# AUDIO_JACK.net
KiCad netlist of a schematic drawn in Altium Designer
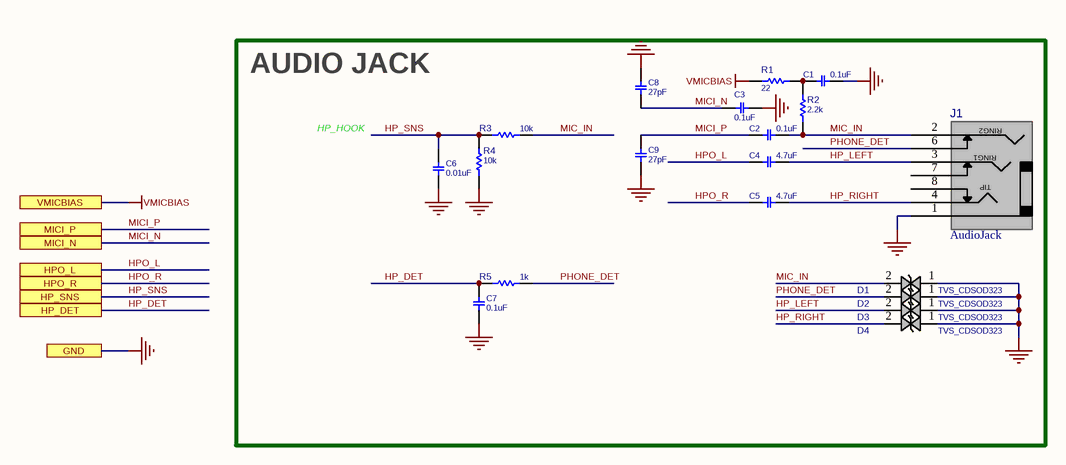
[diagram p0: AUDIO_JACK.SchDoc]

(export (version "E")
  (design (tool "Eeschema 10.0.6"))
  (components
    (comp (ref "C1")
      (value "0.1uF")
      (footprint "C0402")
      (description "CAP, MLCC")
      (fields (field (name "MANF_P#") "GRM155R61E104") (field (name "MANF") "Murata"))
      (libsource (lib "passive_smd") (part "CAP_SMD_MLCC"))
    )
    (comp (ref "C2")
      (value "0.1uF")
      (footprint "C0402")
      (description "CAP, MLCC")
      (fields (field (name "MANF_P#") "GRM155R61E104") (field (name "MANF") "Murata"))
      (libsource (lib "passive_smd") (part "CAP_SMD_MLCC"))
    )
    (comp (ref "C3")
      (value "0.1uF")
      (footprint "C0402")
      (description "CAP, MLCC")
      (fields (field (name "MANF_P#") "GRM155R61E104") (field (name "MANF") "Murata"))
      (libsource (lib "passive_smd") (part "CAP_SMD_MLCC"))
    )
    (comp (ref "C4")
      (value "4.7uF")
      (footprint "C0402")
      (description "CAP, MLCC")
      (fields (field (name "MANF_P#") "CL05A475MP5NRNC") (field (name "MANF") "Samsung"))
      (libsource (lib "mlcc_smd_passive") (part "CAP_SMD_MLCC_100n50TDK"))
    )
    (comp (ref "C5")
      (value "4.7uF")
      (footprint "C0402")
      (description "CAP, MLCC")
      (fields (field (name "MANF_P#") "CL05A475MP5NRNC") (field (name "MANF") "Samsung"))
      (libsource (lib "mlcc_smd_passive") (part "CAP_SMD_MLCC_100n50TDK"))
    )
    (comp (ref "C6")
      (value "0.01uF")
      (footprint "C0402")
      (description "CAP, MLCC")
      (libsource (lib "passive_smd") (part "CAP_SMD_MLCC"))
    )
    (comp (ref "C7")
      (value "0.1uF")
      (footprint "C0402")
      (description "CAP, MLCC")
      (fields (field (name "MANF_P#") "GRM155R61E104") (field (name "MANF") "Murata"))
      (libsource (lib "passive_smd") (part "CAP_SMD_MLCC"))
    )
    (comp (ref "C8")
      (value "27pF")
      (footprint "C0402")
      (description "CAP, MLCC")
      (fields (field (name "MANF_P#") "CC0402JRNPO9BN270") (field (name "MANF") "Yageo"))
      (libsource (lib "passive_smd") (part "CAP_SMD_MLCC"))
    )
    (comp (ref "C9")
      (value "27pF")
      (footprint "C0402")
      (description "CAP, MLCC")
      (fields (field (name "MANF_P#") "CC0402JRNPO9BN270") (field (name "MANF") "Yageo"))
      (libsource (lib "passive_smd") (part "CAP_SMD_MLCC"))
    )
    (comp (ref "D1")
      (value "TVS_CDSOD323")
      (footprint "D0805")
      (description "TVS, ESD PROTECT, Bidirectional")
      (fields (field (name "MANF_P#") "CDSOD323-T12C") (field (name "MANF") "Bourns"))
      (libsource (lib "protect_tvs_esd_fuse") (part "TVS_CDSOD323"))
    )
    (comp (ref "D2")
      (value "TVS_CDSOD323")
      (footprint "D0805")
      (description "TVS, ESD PROTECT, Bidirectional")
      (fields (field (name "MANF_P#") "CDSOD323-T12C") (field (name "MANF") "Bourns"))
      (libsource (lib "protect_tvs_esd_fuse") (part "TVS_CDSOD323"))
    )
    (comp (ref "D3")
      (value "TVS_CDSOD323")
      (footprint "D0805")
      (description "TVS, ESD PROTECT, Bidirectional")
      (fields (field (name "MANF_P#") "CDSOD323-T12C") (field (name "MANF") "Bourns"))
      (libsource (lib "protect_tvs_esd_fuse") (part "TVS_CDSOD323"))
    )
    (comp (ref "D4")
      (value "TVS_CDSOD323")
      (footprint "D0805")
      (description "TVS, ESD PROTECT, Bidirectional")
      (fields (field (name "MANF_P#") "CDSOD323-T12C") (field (name "MANF") "Bourns"))
      (libsource (lib "protect_tvs_esd_fuse") (part "TVS_CDSOD323"))
    )
    (comp (ref "J1")
      (value "AudioJack")
      (footprint "JCKAS_PJ340")
      (description "Jack, Audio, Stereo, 3.5mm, RA, THD")
      (fields (field (name "MANF") "xyfwcn") (field (name "MANF_P#") "PJ-340-SMD"))
      (libsource (lib "conn_jackAV") (part "JACKA3.5SMD_PJ-340-SMD"))
    )
    (comp (ref "R1")
      (value "22")
      (footprint "R0402")
      (description "RESISTOR, SMD")
      (libsource (lib "passive_res_smd") (part "RES_SMD"))
    )
    (comp (ref "R2")
      (value "2.2k")
      (footprint "R0402")
      (description "RESISTOR, SMD")
      (libsource (lib "passive_res_smd") (part "RES_SMD"))
    )
    (comp (ref "R3")
      (value "10k")
      (footprint "R0402")
      (description "RESISTOR, SMD")
      (libsource (lib "passive_res_smd") (part "RES_SMD"))
    )
    (comp (ref "R4")
      (value "10k")
      (footprint "R0402")
      (description "RESISTOR, SMD")
      (libsource (lib "passive_res_smd") (part "RES_SMD"))
    )
    (comp (ref "R5")
      (value "1k")
      (footprint "R0402")
      (description "RESISTOR, SMD")
      (libsource (lib "passive_res_smd") (part "RES_SMD"))
    )
  )
  (nets
    (net (code "1") (name "/HPO_L") (class "Default")
      (node (ref "C4") (pin "1") (pinfunction "1_1") (pintype "passive"))
    )
    (net (code "2") (name "/HPO_R") (class "Default")
      (node (ref "C5") (pin "1") (pinfunction "1_1") (pintype "passive"))
    )
    (net (code "3") (name "/HP_DET") (class "Default")
      (node (ref "C7") (pin "1") (pinfunction "1_1") (pintype "passive"))
      (node (ref "R5") (pin "1") (pinfunction "1_1") (pintype "passive"))
    )
    (net (code "4") (name "/HP_LEFT") (class "Default")
      (node (ref "C4") (pin "2") (pinfunction "2_2") (pintype "passive"))
      (node (ref "D3") (pin "2") (pinfunction "2_2") (pintype "passive"))
      (node (ref "J1") (pin "3") (pinfunction "RING1_3") (pintype "passive"))
    )
    (net (code "5") (name "/HP_RIGHT") (class "Default")
      (node (ref "C5") (pin "2") (pinfunction "2_2") (pintype "passive"))
      (node (ref "D4") (pin "2") (pinfunction "2_2") (pintype "passive"))
      (node (ref "J1") (pin "4") (pinfunction "TIP_4") (pintype "passive"))
    )
    (net (code "6") (name "/HP_SNS") (class "Default")
      (node (ref "C6") (pin "2") (pinfunction "2_2") (pintype "passive"))
      (node (ref "R3") (pin "1") (pinfunction "1_1") (pintype "passive"))
      (node (ref "R4") (pin "1") (pinfunction "1_1") (pintype "passive"))
    )
    (net (code "7") (name "/MICI_N") (class "Default")
      (node (ref "C3") (pin "2") (pinfunction "2_2") (pintype "passive"))
      (node (ref "C8") (pin "2") (pinfunction "2_2") (pintype "passive"))
    )
    (net (code "8") (name "/MICI_P") (class "Default")
      (node (ref "C2") (pin "1") (pinfunction "1_1") (pintype "passive"))
      (node (ref "C9") (pin "1") (pinfunction "1_1") (pintype "passive"))
    )
    (net (code "9") (name "/MIC_IN") (class "Default")
      (node (ref "C2") (pin "2") (pinfunction "2_2") (pintype "passive"))
      (node (ref "D1") (pin "2") (pinfunction "2_2") (pintype "passive"))
      (node (ref "J1") (pin "2") (pinfunction "RING2_2") (pintype "passive"))
      (node (ref "R2") (pin "2") (pinfunction "2_2") (pintype "passive"))
      (node (ref "R3") (pin "2") (pinfunction "2_2") (pintype "passive"))
    )
    (net (code "10") (name "/PHONE_DET") (class "Default")
      (node (ref "D2") (pin "2") (pinfunction "2_2") (pintype "passive"))
      (node (ref "J1") (pin "6") (pinfunction "RING2SW_6") (pintype "passive"))
      (node (ref "R5") (pin "2") (pinfunction "2_2") (pintype "passive"))
    )
    (net (code "11") (name "GND") (class "Default")
      (node (ref "C1") (pin "1") (pinfunction "1_1") (pintype "passive"))
      (node (ref "C3") (pin "1") (pinfunction "1_1") (pintype "passive"))
      (node (ref "C6") (pin "1") (pinfunction "1_1") (pintype "passive"))
      (node (ref "C7") (pin "2") (pinfunction "2_2") (pintype "passive"))
      (node (ref "C8") (pin "1") (pinfunction "1_1") (pintype "passive"))
      (node (ref "C9") (pin "2") (pinfunction "2_2") (pintype "passive"))
      (node (ref "D1") (pin "1") (pinfunction "1_1") (pintype "passive"))
      (node (ref "D2") (pin "1") (pinfunction "1_1") (pintype "passive"))
      (node (ref "D3") (pin "1") (pinfunction "1_1") (pintype "passive"))
      (node (ref "D4") (pin "1") (pinfunction "1_1") (pintype "passive"))
      (node (ref "J1") (pin "1") (pinfunction "SLEEVE_1") (pintype "passive"))
      (node (ref "R4") (pin "2") (pinfunction "2_2") (pintype "passive"))
    )
    (net (code "12") (name "Net-(C1-Pad2)") (class "Default")
      (node (ref "C1") (pin "2") (pinfunction "2_2") (pintype "passive"))
      (node (ref "R1") (pin "2") (pinfunction "2_2") (pintype "passive"))
      (node (ref "R2") (pin "1") (pinfunction "1_1") (pintype "passive"))
    )
    (net (code "13") (name "VMICBIAS") (class "Default")
      (node (ref "R1") (pin "1") (pinfunction "1_1") (pintype "passive"))
    )
    (net (code "14") (name "unconnected-(J1-RING1SW-Pad7)") (class "Default")
      (node (ref "J1") (pin "7") (pinfunction "RING1SW_7") (pintype "passive"))
    )
    (net (code "15") (name "unconnected-(J1-TIPSW-Pad8)") (class "Default")
      (node (ref "J1") (pin "8") (pinfunction "TIPSW_8") (pintype "passive"))
    )
  )
)
